# Mems.net
KiCad netlist of a schematic drawn in Altium Designer
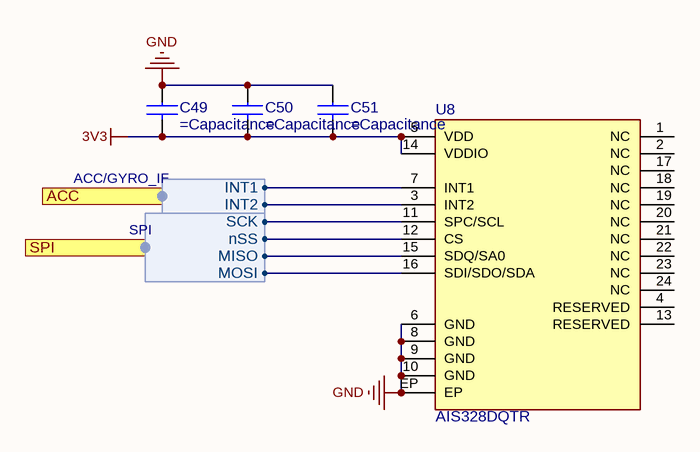
[diagram p0: Mems.SchDoc]

(export (version "E")
  (design (tool "Eeschema 10.0.6"))
  (components
    (comp (ref "C49")
      (value "~")
      (footprint "C0402")
      (description "Multilayer Ceramic Capacitors MLCC - SMD/SMT 0402 1uF 25volts *Derate Voltage/Temp")
      (fields
        (field (name "MANUFACTURER") "Murata")
        (field (name "MANUFACTURER PART NUMBER") "GRM155C81E105KE11J")
      )
      (libsource (lib "Capacitors") (part "CAP0402-1uF-25V"))
    )
    (comp (ref "C50")
      (value "~")
      (footprint "C0402")
      (description "CAP CER 0.1UF 50V X7R 0402")
      (fields
        (field (name "MANUFACTURER") "Walsin Technologies")
        (field (name "MANUFACTURER PART NUMBER") "0402B104K500CT")
      )
      (libsource (lib "Capacitors") (part "CAP0402-0.1uF-50V"))
    )
    (comp (ref "C51")
      (value "~")
      (footprint "C0402")
      (description "CAP CER 0.1UF 50V X7R 0402")
      (fields
        (field (name "MANUFACTURER") "Walsin Technologies")
        (field (name "MANUFACTURER PART NUMBER") "0402B104K500CT")
      )
      (libsource (lib "Capacitors") (part "CAP0402-0.1uF-50V"))
    )
    (comp (ref "U8")
      (value "AIS328DQTR")
      (footprint "VQFN24")
      (description "High-performance ultra low-power 3-axis accelerometer ¦ ACCELEROMETER 2-8G I2C/SPI 24QFN")
      (fields (field (name "MANUFACTURER") "STMicroelectronics"))
      (libsource (lib "HerosLib") (part "AIS328DQTR"))
    )
  )
  (nets
    (net (code "3") (name "/INT1") (class "Default")
      (node (ref "U8") (pin "7") (pinfunction "INT1_7") (pintype "passive"))
    )
    (net (code "4") (name "/INT2") (class "Default")
      (node (ref "U8") (pin "3") (pinfunction "INT2_3") (pintype "passive"))
    )
    (net (code "5") (name "/MISO") (class "Default")
      (node (ref "U8") (pin "15") (pinfunction "SDQ/SA0_15") (pintype "passive"))
    )
    (net (code "6") (name "/MOSI") (class "Default")
      (node (ref "U8") (pin "16") (pinfunction "SDI/SDO/SDA_16") (pintype "passive"))
    )
    (net (code "7") (name "/SCK") (class "Default")
      (node (ref "U8") (pin "11") (pinfunction "SPC/SCL_11") (pintype "passive"))
    )
    (net (code "8") (name "/nSS") (class "Default")
      (node (ref "U8") (pin "12") (pinfunction "CS_12") (pintype "passive"))
    )
    (net (code "11") (name "3V3") (class "Default")
      (node (ref "C49") (pin "2") (pinfunction "2_2") (pintype "passive"))
      (node (ref "C50") (pin "2") (pinfunction "2_2") (pintype "passive"))
      (node (ref "C51") (pin "2") (pinfunction "2_2") (pintype "passive"))
      (node (ref "U8") (pin "14") (pinfunction "VDDIO_14") (pintype "passive"))
      (node (ref "U8") (pin "5") (pinfunction "VDD_5") (pintype "passive"))
    )
    (net (code "12") (name "GND") (class "Default")
      (node (ref "C49") (pin "1") (pinfunction "1_1") (pintype "passive"))
      (node (ref "C50") (pin "1") (pinfunction "1_1") (pintype "passive"))
      (node (ref "C51") (pin "1") (pinfunction "1_1") (pintype "passive"))
      (node (ref "U8") (pin "10") (pinfunction "GND_10") (pintype "passive"))
      (node (ref "U8") (pin "6") (pinfunction "GND_6") (pintype "passive"))
      (node (ref "U8") (pin "8") (pinfunction "GND_8") (pintype "passive"))
      (node (ref "U8") (pin "9") (pinfunction "GND_9") (pintype "passive"))
      (node (ref "U8") (pin "EP") (pinfunction "EP_EP") (pintype "passive"))
    )
    (net (code "13") (name "unconnected-(U8-NC-Pad1)") (class "Default")
      (node (ref "U8") (pin "1") (pinfunction "NC_1") (pintype "passive"))
    )
    (net (code "14") (name "unconnected-(U8-NC-Pad2)") (class "Default")
      (node (ref "U8") (pin "2") (pinfunction "NC_2") (pintype "passive"))
    )
    (net (code "15") (name "unconnected-(U8-NC-Pad17)") (class "Default")
      (node (ref "U8") (pin "17") (pinfunction "NC_17") (pintype "passive"))
    )
    (net (code "16") (name "unconnected-(U8-NC-Pad18)") (class "Default")
      (node (ref "U8") (pin "18") (pinfunction "NC_18") (pintype "passive"))
    )
    (net (code "17") (name "unconnected-(U8-NC-Pad19)") (class "Default")
      (node (ref "U8") (pin "19") (pinfunction "NC_19") (pintype "passive"))
    )
    (net (code "18") (name "unconnected-(U8-NC-Pad20)") (class "Default")
      (node (ref "U8") (pin "20") (pinfunction "NC_20") (pintype "passive"))
    )
    (net (code "19") (name "unconnected-(U8-NC-Pad21)") (class "Default")
      (node (ref "U8") (pin "21") (pinfunction "NC_21") (pintype "passive"))
    )
    (net (code "20") (name "unconnected-(U8-NC-Pad22)") (class "Default")
      (node (ref "U8") (pin "22") (pinfunction "NC_22") (pintype "passive"))
    )
    (net (code "21") (name "unconnected-(U8-NC-Pad23)") (class "Default")
      (node (ref "U8") (pin "23") (pinfunction "NC_23") (pintype "passive"))
    )
    (net (code "22") (name "unconnected-(U8-NC-Pad24)") (class "Default")
      (node (ref "U8") (pin "24") (pinfunction "NC_24") (pintype "passive"))
    )
    (net (code "23") (name "unconnected-(U8-RESERVED-Pad4)") (class "Default")
      (node (ref "U8") (pin "4") (pinfunction "RESERVED_4") (pintype "passive"))
    )
    (net (code "24") (name "unconnected-(U8-RESERVED-Pad13)") (class "Default")
      (node (ref "U8") (pin "13") (pinfunction "RESERVED_13") (pintype "passive"))
    )
  )
)
